# CANLink_revA.net
KiCad netlist of a schematic drawn in Altium Designer
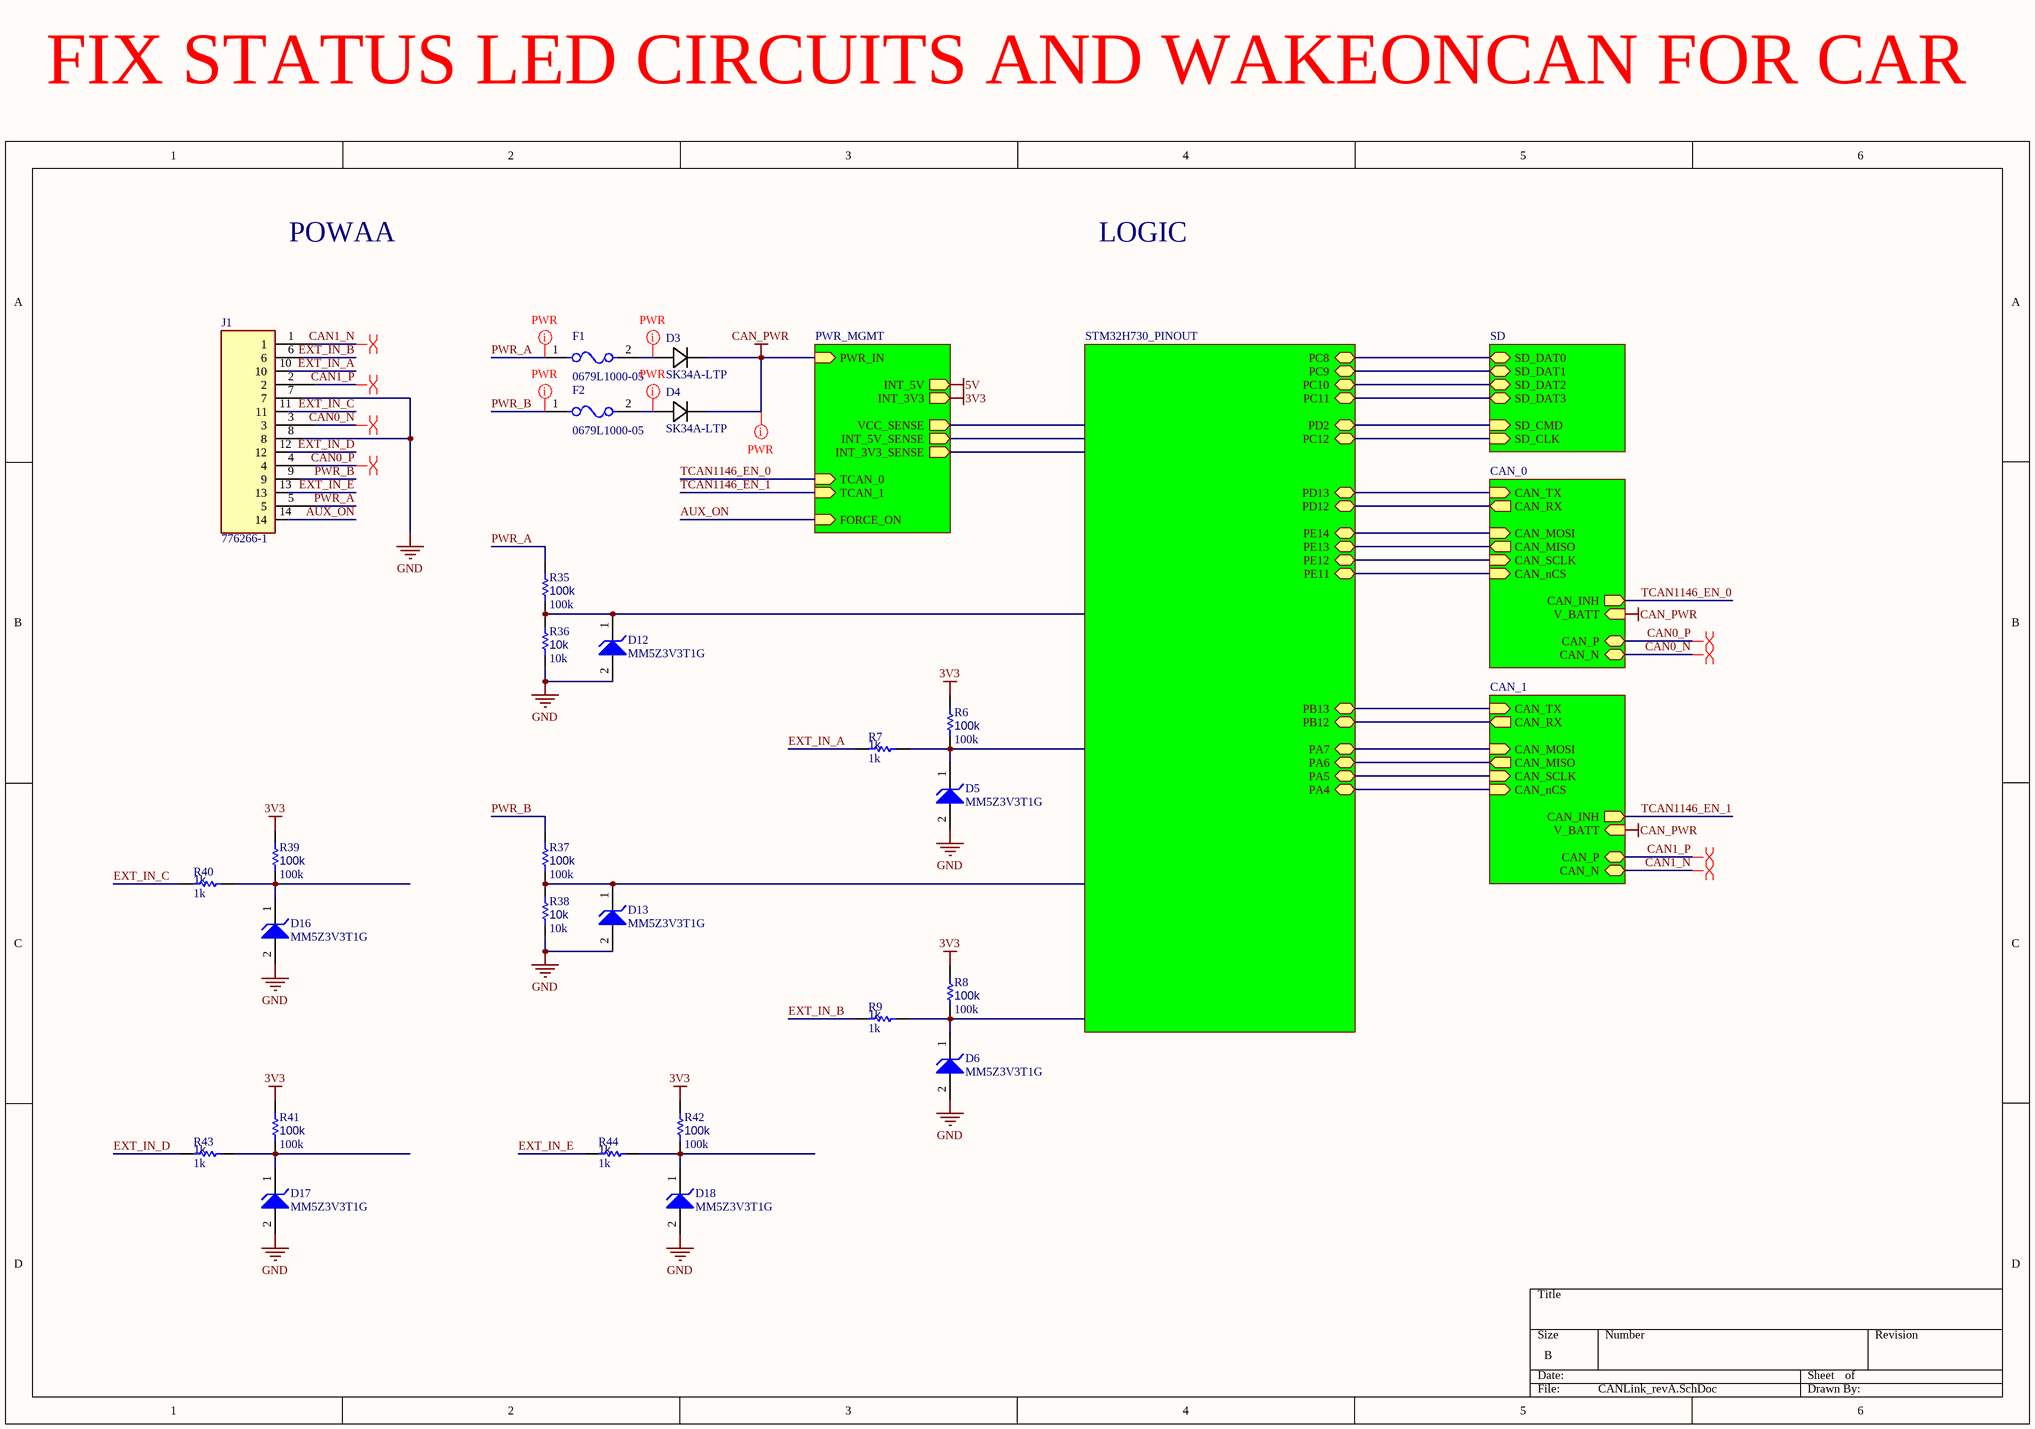
[diagram p0: CANLink_revA.SchDoc]

(export (version "E")
  (design (tool "Eeschema 10.0.6"))
  (components
    (comp (ref "D3")
      (value "SK34A-LTP")
      (footprint "SK34A-LTP-Footprint-1")
      (description "Rectifier Diode, Schottky, 1 Phase, 1 Element, 3A, 40V V(RRM), Silicon, DO-214AC")
      (libsource (lib "Space Concordia") (part "SK34A-LTP"))
    )
    (comp (ref "D4")
      (value "SK34A-LTP")
      (footprint "SK34A-LTP-Footprint-1")
      (description "Rectifier Diode, Schottky, 1 Phase, 1 Element, 3A, 40V V(RRM), Silicon, DO-214AC")
      (libsource (lib "Space Concordia") (part "SK34A-LTP"))
    )
    (comp (ref "D5")
      (value "MM5Z3V3T1G")
      (footprint "ONSC-SOD-523-2-502-01_V")
      (description "Zener Voltage Regulator, 500 mW, 2-Pin SOD-523, Pb-Free, Tape and Reel")
      (fields (field (name "MANUFACTURER") "On Semiconductor"))
      (libsource (lib "Altium Content Vault") (part "ONSC-K1A2-2"))
    )
    (comp (ref "D6")
      (value "MM5Z3V3T1G")
      (footprint "ONSC-SOD-523-2-502-01_V")
      (description "Zener Voltage Regulator, 500 mW, 2-Pin SOD-523, Pb-Free, Tape and Reel")
      (fields (field (name "MANUFACTURER") "On Semiconductor"))
      (libsource (lib "Altium Content Vault") (part "ONSC-K1A2-2"))
    )
    (comp (ref "D12")
      (value "MM5Z3V3T1G")
      (footprint "ONSC-SOD-523-2-502-01_V")
      (description "Zener Voltage Regulator, 500 mW, 2-Pin SOD-523, Pb-Free, Tape and Reel")
      (fields (field (name "MANUFACTURER") "On Semiconductor"))
      (libsource (lib "Altium Content Vault") (part "ONSC-K1A2-2"))
    )
    (comp (ref "D13")
      (value "MM5Z3V3T1G")
      (footprint "ONSC-SOD-523-2-502-01_V")
      (description "Zener Voltage Regulator, 500 mW, 2-Pin SOD-523, Pb-Free, Tape and Reel")
      (fields (field (name "MANUFACTURER") "On Semiconductor"))
      (libsource (lib "Altium Content Vault") (part "ONSC-K1A2-2"))
    )
    (comp (ref "D16")
      (value "MM5Z3V3T1G")
      (footprint "ONSC-SOD-523-2-502-01_V")
      (description "Zener Voltage Regulator, 500 mW, 2-Pin SOD-523, Pb-Free, Tape and Reel")
      (fields (field (name "MANUFACTURER") "On Semiconductor"))
      (libsource (lib "Altium Content Vault") (part "ONSC-K1A2-2"))
    )
    (comp (ref "D17")
      (value "MM5Z3V3T1G")
      (footprint "ONSC-SOD-523-2-502-01_V")
      (description "Zener Voltage Regulator, 500 mW, 2-Pin SOD-523, Pb-Free, Tape and Reel")
      (fields (field (name "MANUFACTURER") "On Semiconductor"))
      (libsource (lib "Altium Content Vault") (part "ONSC-K1A2-2"))
    )
    (comp (ref "D18")
      (value "MM5Z3V3T1G")
      (footprint "ONSC-SOD-523-2-502-01_V")
      (description "Zener Voltage Regulator, 500 mW, 2-Pin SOD-523, Pb-Free, Tape and Reel")
      (fields (field (name "MANUFACTURER") "On Semiconductor"))
      (libsource (lib "Altium Content Vault") (part "ONSC-K1A2-2"))
    )
    (comp (ref "F1")
      (value "0679L1000-05")
      (footprint "FP-0679L-MFG")
      (description "DIFF P#!!!\r\n\r\nFUSE BRD MNT 1A 125VAC/VDC")
      (fields
        (field (name "OCTOPART") "https://octopart.com/0679l9150-01-bel+fuse-70850665")
        (field (name "MANUFACTURER") "Bel Fuse")
      )
      (libsource (lib "Altium Content Vault") (part "5bcf9b9f640e542cf0359d10258e979"))
    )
    (comp (ref "F2")
      (value "0679L1000-05")
      (footprint "FP-0679L-MFG")
      (description "DIFF P#!!!\r\n\r\nFUSE BRD MNT 1A 125VAC/VDC")
      (fields
        (field (name "OCTOPART") "https://octopart.com/0679l9150-01-bel+fuse-70850665")
        (field (name "MANUFACTURER") "Bel Fuse")
      )
      (libsource (lib "Altium Content Vault") (part "5bcf9b9f640e542cf0359d10258e979"))
    )
    (comp (ref "J1")
      (value "776266-1")
      (footprint "776266-1-Footprint-1")
      (description "Board Connector")
      (libsource (lib "Space Concordia") (part "776266-1"))
    )
    (comp (ref "R6")
      (value "100k")
      (footprint "R0603B")
      (description "Resistor")
      (fields (field (name "ALTIUM_VALUE") "100k"))
      (libsource (lib "Space Concordia") (part "Resistor"))
    )
    (comp (ref "R7")
      (value "1k")
      (footprint "R0603B")
      (description "Resistor")
      (fields (field (name "ALTIUM_VALUE") "1k"))
      (libsource (lib "Space Concordia") (part "Resistor"))
    )
    (comp (ref "R8")
      (value "100k")
      (footprint "R0603B")
      (description "Resistor")
      (fields (field (name "ALTIUM_VALUE") "100k"))
      (libsource (lib "Space Concordia") (part "Resistor"))
    )
    (comp (ref "R9")
      (value "1k")
      (footprint "R0603B")
      (description "Resistor")
      (fields (field (name "ALTIUM_VALUE") "1k"))
      (libsource (lib "Space Concordia") (part "Resistor"))
    )
    (comp (ref "R35")
      (value "100k")
      (footprint "R0603B")
      (description "Resistor")
      (fields (field (name "ALTIUM_VALUE") "100k"))
      (libsource (lib "Space Concordia") (part "Resistor"))
    )
    (comp (ref "R36")
      (value "10k")
      (footprint "R0603B")
      (description "Resistor")
      (fields (field (name "ALTIUM_VALUE") "10k"))
      (libsource (lib "Space Concordia") (part "Resistor"))
    )
    (comp (ref "R37")
      (value "100k")
      (footprint "R0603B")
      (description "Resistor")
      (fields (field (name "ALTIUM_VALUE") "100k"))
      (libsource (lib "Space Concordia") (part "Resistor"))
    )
    (comp (ref "R38")
      (value "10k")
      (footprint "R0603B")
      (description "Resistor")
      (fields (field (name "ALTIUM_VALUE") "10k"))
      (libsource (lib "Space Concordia") (part "Resistor"))
    )
    (comp (ref "R39")
      (value "100k")
      (footprint "R0603B")
      (description "Resistor")
      (fields (field (name "ALTIUM_VALUE") "100k"))
      (libsource (lib "Space Concordia") (part "Resistor"))
    )
    (comp (ref "R40")
      (value "1k")
      (footprint "R0603B")
      (description "Resistor")
      (fields (field (name "ALTIUM_VALUE") "1k"))
      (libsource (lib "Space Concordia") (part "Resistor"))
    )
    (comp (ref "R41")
      (value "100k")
      (footprint "R0603B")
      (description "Resistor")
      (fields (field (name "ALTIUM_VALUE") "100k"))
      (libsource (lib "Space Concordia") (part "Resistor"))
    )
    (comp (ref "R42")
      (value "100k")
      (footprint "R0603B")
      (description "Resistor")
      (fields (field (name "ALTIUM_VALUE") "100k"))
      (libsource (lib "Space Concordia") (part "Resistor"))
    )
    (comp (ref "R43")
      (value "1k")
      (footprint "R0603B")
      (description "Resistor")
      (fields (field (name "ALTIUM_VALUE") "1k"))
      (libsource (lib "Space Concordia") (part "Resistor"))
    )
    (comp (ref "R44")
      (value "1k")
      (footprint "R0603B")
      (description "Resistor")
      (fields (field (name "ALTIUM_VALUE") "1k"))
      (libsource (lib "Space Concordia") (part "Resistor"))
    )
  )
  (nets
    (net (code "1") (name "/AUX_ON") (class "Default")
      (node (ref "J1") (pin "14") (pinfunction "14_14") (pintype "passive"))
    )
    (net (code "2") (name "/CAN0_N") (class "Default")
      (node (ref "J1") (pin "3") (pinfunction "3_3") (pintype "passive"))
    )
    (net (code "3") (name "/CAN0_P") (class "Default")
      (node (ref "J1") (pin "4") (pinfunction "4_4") (pintype "passive"))
    )
    (net (code "4") (name "/CAN1_N") (class "Default")
      (node (ref "J1") (pin "1") (pinfunction "1_1") (pintype "passive"))
    )
    (net (code "5") (name "/CAN1_P") (class "Default")
      (node (ref "J1") (pin "2") (pinfunction "2_2") (pintype "passive"))
    )
    (net (code "18") (name "/EXT_IN_A") (class "Default")
      (node (ref "J1") (pin "10") (pinfunction "10_10") (pintype "passive"))
      (node (ref "R7") (pin "2") (pinfunction "2_2") (pintype "passive"))
    )
    (net (code "19") (name "/EXT_IN_B") (class "Default")
      (node (ref "J1") (pin "6") (pinfunction "6_6") (pintype "passive"))
      (node (ref "R9") (pin "2") (pinfunction "2_2") (pintype "passive"))
    )
    (net (code "20") (name "/EXT_IN_C") (class "Default")
      (node (ref "J1") (pin "11") (pinfunction "11_11") (pintype "passive"))
      (node (ref "R40") (pin "2") (pinfunction "2_2") (pintype "passive"))
    )
    (net (code "21") (name "/EXT_IN_D") (class "Default")
      (node (ref "J1") (pin "12") (pinfunction "12_12") (pintype "passive"))
      (node (ref "R43") (pin "2") (pinfunction "2_2") (pintype "passive"))
    )
    (net (code "22") (name "/EXT_IN_E") (class "Default")
      (node (ref "J1") (pin "13") (pinfunction "13_13") (pintype "passive"))
      (node (ref "R44") (pin "2") (pinfunction "2_2") (pintype "passive"))
    )
    (net (code "31") (name "/PWR_A") (class "Default")
      (node (ref "F1") (pin "1") (pinfunction "1_1") (pintype "passive"))
      (node (ref "J1") (pin "5") (pinfunction "5_5") (pintype "passive"))
      (node (ref "R35") (pin "1") (pinfunction "1_1") (pintype "passive"))
    )
    (net (code "32") (name "/PWR_B") (class "Default")
      (node (ref "F2") (pin "1") (pinfunction "1_1") (pintype "passive"))
      (node (ref "J1") (pin "9") (pinfunction "9_9") (pintype "passive"))
      (node (ref "R37") (pin "1") (pinfunction "1_1") (pintype "passive"))
    )
    (net (code "36") (name "3V3") (class "Default")
      (node (ref "R39") (pin "1") (pinfunction "1_1") (pintype "passive"))
      (node (ref "R41") (pin "1") (pinfunction "1_1") (pintype "passive"))
      (node (ref "R42") (pin "1") (pinfunction "1_1") (pintype "passive"))
      (node (ref "R6") (pin "1") (pinfunction "1_1") (pintype "passive"))
      (node (ref "R8") (pin "1") (pinfunction "1_1") (pintype "passive"))
    )
    (net (code "38") (name "CAN_PWR") (class "Default")
      (node (ref "D3") (pin "1") (pinfunction "CATHODE_1") (pintype "passive"))
      (node (ref "D4") (pin "1") (pinfunction "CATHODE_1") (pintype "passive"))
    )
    (net (code "39") (name "GND") (class "Default")
      (node (ref "D12") (pin "2") (pinfunction "A_2") (pintype "passive"))
      (node (ref "D13") (pin "2") (pinfunction "A_2") (pintype "passive"))
      (node (ref "D16") (pin "2") (pinfunction "A_2") (pintype "passive"))
      (node (ref "D17") (pin "2") (pinfunction "A_2") (pintype "passive"))
      (node (ref "D18") (pin "2") (pinfunction "A_2") (pintype "passive"))
      (node (ref "D5") (pin "2") (pinfunction "A_2") (pintype "passive"))
      (node (ref "D6") (pin "2") (pinfunction "A_2") (pintype "passive"))
      (node (ref "J1") (pin "7") (pinfunction "7_7") (pintype "passive"))
      (node (ref "J1") (pin "8") (pinfunction "8_8") (pintype "passive"))
      (node (ref "R36") (pin "2") (pinfunction "2_2") (pintype "passive"))
      (node (ref "R38") (pin "2") (pinfunction "2_2") (pintype "passive"))
    )
    (net (code "40") (name "Net-(D3-ANODE)") (class "Default")
      (node (ref "D3") (pin "2") (pinfunction "ANODE_2") (pintype "passive"))
      (node (ref "F1") (pin "2") (pinfunction "2_2") (pintype "passive"))
    )
    (net (code "41") (name "Net-(D4-ANODE)") (class "Default")
      (node (ref "D4") (pin "2") (pinfunction "ANODE_2") (pintype "passive"))
      (node (ref "F2") (pin "2") (pinfunction "2_2") (pintype "passive"))
    )
    (net (code "42") (name "Net-(D5-K)") (class "Default")
      (node (ref "D5") (pin "1") (pinfunction "K_1") (pintype "passive"))
      (node (ref "R6") (pin "2") (pinfunction "2_2") (pintype "passive"))
      (node (ref "R7") (pin "1") (pinfunction "1_1") (pintype "passive"))
    )
    (net (code "43") (name "Net-(D6-K)") (class "Default")
      (node (ref "D6") (pin "1") (pinfunction "K_1") (pintype "passive"))
      (node (ref "R8") (pin "2") (pinfunction "2_2") (pintype "passive"))
      (node (ref "R9") (pin "1") (pinfunction "1_1") (pintype "passive"))
    )
    (net (code "44") (name "Net-(D12-K)") (class "Default")
      (node (ref "D12") (pin "1") (pinfunction "K_1") (pintype "passive"))
      (node (ref "R35") (pin "2") (pinfunction "2_2") (pintype "passive"))
      (node (ref "R36") (pin "1") (pinfunction "1_1") (pintype "passive"))
    )
    (net (code "45") (name "Net-(D13-K)") (class "Default")
      (node (ref "D13") (pin "1") (pinfunction "K_1") (pintype "passive"))
      (node (ref "R37") (pin "2") (pinfunction "2_2") (pintype "passive"))
      (node (ref "R38") (pin "1") (pinfunction "1_1") (pintype "passive"))
    )
    (net (code "46") (name "Net-(D16-K)") (class "Default")
      (node (ref "D16") (pin "1") (pinfunction "K_1") (pintype "passive"))
      (node (ref "R39") (pin "2") (pinfunction "2_2") (pintype "passive"))
      (node (ref "R40") (pin "1") (pinfunction "1_1") (pintype "passive"))
    )
    (net (code "47") (name "Net-(D17-K)") (class "Default")
      (node (ref "D17") (pin "1") (pinfunction "K_1") (pintype "passive"))
      (node (ref "R41") (pin "2") (pinfunction "2_2") (pintype "passive"))
      (node (ref "R43") (pin "1") (pinfunction "1_1") (pintype "passive"))
    )
    (net (code "48") (name "Net-(D18-K)") (class "Default")
      (node (ref "D18") (pin "1") (pinfunction "K_1") (pintype "passive"))
      (node (ref "R42") (pin "2") (pinfunction "2_2") (pintype "passive"))
      (node (ref "R44") (pin "1") (pinfunction "1_1") (pintype "passive"))
    )
  )
)
